# Arduino_Electronic_Load_Ver03.net
KiCad netlist of a schematic drawn in EAGLE
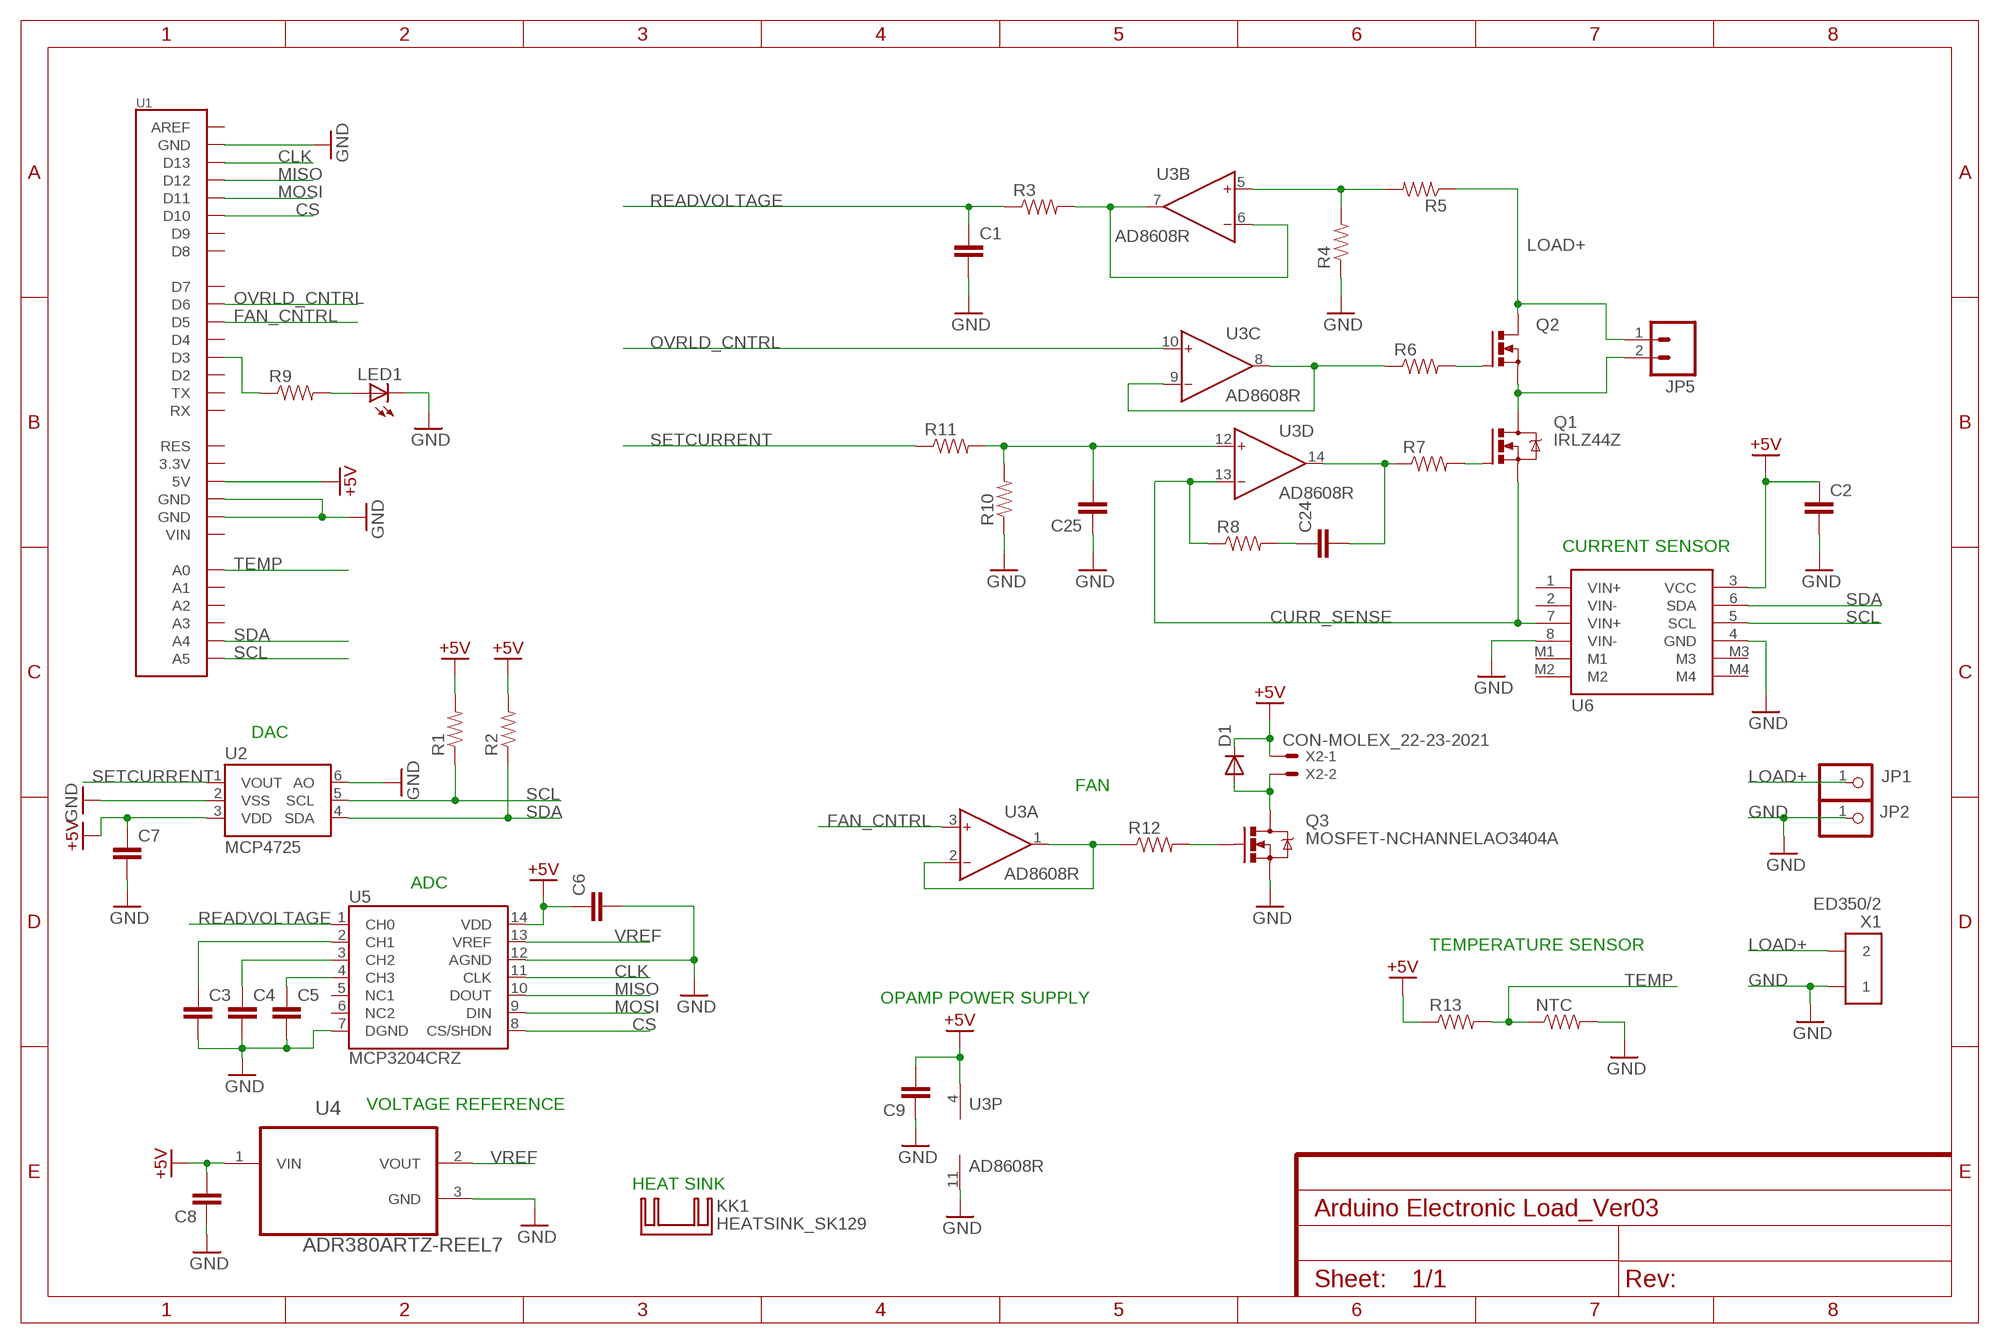
[diagram p0: schematic, sheet 1]

(export (version "E")
  (design (tool "Eeschema 10.0.6"))
  (components
    (comp (ref "C1")
      (value "CAP0603-CAP")
      (footprint "eagle-import:0603-CAP")
      (libsource (lib "eagle-import") (part "CAP0603-CAP"))
    )
    (comp (ref "C2")
      (value "CAP0603-CAP")
      (footprint "eagle-import:0603-CAP")
      (libsource (lib "eagle-import") (part "CAP0603-CAP"))
    )
    (comp (ref "C3")
      (value "CAP0603-CAP")
      (footprint "eagle-import:0603-CAP")
      (libsource (lib "eagle-import") (part "CAP0603-CAP"))
    )
    (comp (ref "C4")
      (value "CAP0603-CAP")
      (footprint "eagle-import:0603-CAP")
      (libsource (lib "eagle-import") (part "CAP0603-CAP"))
    )
    (comp (ref "C5")
      (value "CAP0603-CAP")
      (footprint "eagle-import:0603-CAP")
      (libsource (lib "eagle-import") (part "CAP0603-CAP"))
    )
    (comp (ref "C6")
      (value "CAP0603-CAP")
      (footprint "eagle-import:0603-CAP")
      (libsource (lib "eagle-import") (part "CAP0603-CAP"))
    )
    (comp (ref "C7")
      (value "CAP0603-CAP")
      (footprint "eagle-import:0603-CAP")
      (libsource (lib "eagle-import") (part "CAP0603-CAP"))
    )
    (comp (ref "C8")
      (value "CAP0603-CAP")
      (footprint "eagle-import:0603-CAP")
      (libsource (lib "eagle-import") (part "CAP0603-CAP"))
    )
    (comp (ref "C9")
      (value "CAP0603-CAP")
      (footprint "eagle-import:0603-CAP")
      (libsource (lib "eagle-import") (part "CAP0603-CAP"))
    )
    (comp (ref "C24")
      (value "CAP0603-CAP")
      (footprint "eagle-import:0603-CAP")
      (libsource (lib "eagle-import") (part "CAP0603-CAP"))
    )
    (comp (ref "C25")
      (value "CAP0603-CAP")
      (footprint "eagle-import:0603-CAP")
      (libsource (lib "eagle-import") (part "CAP0603-CAP"))
    )
    (comp (ref "D1")
      (value "DIODEPTH")
      (footprint "eagle-import:DIODE-1N4001")
      (libsource (lib "eagle-import") (part "DIODEPTH"))
    )
    (comp (ref "JP1")
      (value "PINHEAD_PINHD-1X1")
      (footprint "eagle-import:PINHEAD_1X01")
      (libsource (lib "eagle-import") (part "PINHEAD_PINHD-1X1"))
    )
    (comp (ref "JP2")
      (value "PINHEAD_PINHD-1X1")
      (footprint "eagle-import:PINHEAD_1X01")
      (libsource (lib "eagle-import") (part "PINHEAD_PINHD-1X1"))
    )
    (comp (ref "JP5")
      (value "M02")
      (footprint "eagle-import:1X02_LONGPADS")
      (libsource (lib "eagle-import") (part "M02"))
    )
    (comp (ref "KK1")
      (value "HEATSINK_SK129")
      (footprint "eagle-import:HEATSINK_SK129-HOLE")
      (libsource (lib "eagle-import") (part "HEATSINK_SK129"))
    )
    (comp (ref "LED1")
      (value "LED5MM")
      (footprint "eagle-import:LED5MM")
      (libsource (lib "eagle-import") (part "LED5MM"))
    )
    (comp (ref "NTC")
      (value "RESISTOR0402-RES")
      (footprint "eagle-import:0402-RES")
      (libsource (lib "eagle-import") (part "RESISTOR0402-RES"))
    )
    (comp (ref "Q1")
      (value "IRLZ44Z")
      (footprint "eagle-import:TO220BV_1")
      (libsource (lib "eagle-import") (part "IRLZ44Z"))
    )
    (comp (ref "Q2")
      (value "PMOSFET_NTO220BV")
      (footprint "eagle-import:TO220BV")
      (libsource (lib "eagle-import") (part "PMOSFET_NTO220BV"))
    )
    (comp (ref "Q3")
      (value "MOSFET-NCHANNELAO3404A")
      (footprint "eagle-import:SOT23-3")
      (libsource (lib "eagle-import") (part "MOSFET-NCHANNELAO3404A"))
    )
    (comp (ref "R1")
      (value "RESISTOR0603-RES")
      (footprint "eagle-import:0603-RES")
      (libsource (lib "eagle-import") (part "RESISTOR0603-RES"))
    )
    (comp (ref "R2")
      (value "RESISTOR0603-RES")
      (footprint "eagle-import:0603-RES")
      (libsource (lib "eagle-import") (part "RESISTOR0603-RES"))
    )
    (comp (ref "R3")
      (value "RESISTOR0603-RES")
      (footprint "eagle-import:0603-RES")
      (libsource (lib "eagle-import") (part "RESISTOR0603-RES"))
    )
    (comp (ref "R4")
      (value "RESISTOR0603-RES")
      (footprint "eagle-import:0603-RES")
      (libsource (lib "eagle-import") (part "RESISTOR0603-RES"))
    )
    (comp (ref "R5")
      (value "RESISTOR0603-RES")
      (footprint "eagle-import:0603-RES")
      (libsource (lib "eagle-import") (part "RESISTOR0603-RES"))
    )
    (comp (ref "R6")
      (value "RESISTOR0603-RES")
      (footprint "eagle-import:0603-RES")
      (libsource (lib "eagle-import") (part "RESISTOR0603-RES"))
    )
    (comp (ref "R7")
      (value "RESISTOR0603-RES")
      (footprint "eagle-import:0603-RES")
      (libsource (lib "eagle-import") (part "RESISTOR0603-RES"))
    )
    (comp (ref "R8")
      (value "RESISTOR0603-RES")
      (footprint "eagle-import:0603-RES")
      (libsource (lib "eagle-import") (part "RESISTOR0603-RES"))
    )
    (comp (ref "R9")
      (value "RESISTOR0603-RES")
      (footprint "eagle-import:0603-RES")
      (libsource (lib "eagle-import") (part "RESISTOR0603-RES"))
    )
    (comp (ref "R10")
      (value "RESISTOR0603-RES")
      (footprint "eagle-import:0603-RES")
      (libsource (lib "eagle-import") (part "RESISTOR0603-RES"))
    )
    (comp (ref "R11")
      (value "RESISTOR0603-RES")
      (footprint "eagle-import:0603-RES")
      (libsource (lib "eagle-import") (part "RESISTOR0603-RES"))
    )
    (comp (ref "R12")
      (value "RESISTOR0603-RES")
      (footprint "eagle-import:0603-RES")
      (libsource (lib "eagle-import") (part "RESISTOR0603-RES"))
    )
    (comp (ref "R13")
      (value "RESISTOR0603-RES")
      (footprint "eagle-import:0603-RES")
      (libsource (lib "eagle-import") (part "RESISTOR0603-RES"))
    )
    (comp (ref "U1")
      (value "ARDUINO_SHIELD")
      (footprint "eagle-import:DUEMILANOVE_SHIELD")
      (libsource (lib "eagle-import") (part "ARDUINO_SHIELD"))
    )
    (comp (ref "U2")
      (value "MCP4725")
      (footprint "eagle-import:SOT23-6")
      (libsource (lib "eagle-import") (part "MCP4725SOT-23"))
    )
    (comp (ref "U3")
      (value "AD8608R")
      (footprint "eagle-import:SO14")
      (libsource (lib "eagle-import") (part "AD8608R"))
    )
    (comp (ref "U4")
      (value "ADR380ARTZ-REEL7")
      (footprint "eagle-import:SOT95P237X112-3N")
      (libsource (lib "eagle-import") (part "ADR380ARTZ-REEL7"))
    )
    (comp (ref "U5")
      (value "MCP3204CRZ")
      (footprint "eagle-import:SOIC-14")
      (libsource (lib "eagle-import") (part "MCP3204CRZ"))
    )
    (comp (ref "U6")
      (value "INA219")
      (footprint "eagle-import:INA219")
      (libsource (lib "eagle-import") (part "INA219"))
    )
    (comp (ref "X1")
      (value "ED350/2")
      (footprint "eagle-import:ED350_2")
      (libsource (lib "eagle-import") (part "ED350/2"))
    )
    (comp (ref "X2")
      (value "CON-MOLEX_22-23-2021")
      (footprint "eagle-import:CON-MOLEX_22-23-2021")
      (fields (field (name "MF") "MOLEX") (field (name "MPN") "22-23-2021"))
      (libsource (lib "eagle-import") (part "CON-MOLEX_22-23-2021"))
    )
  )
  (nets
    (net (code "1") (name "+5V") (class "Default")
      (node (ref "C2") (pin "1") (pinfunction "1_1") (pintype "passive"))
      (node (ref "C6") (pin "1") (pinfunction "1_1") (pintype "passive"))
      (node (ref "C7") (pin "1") (pinfunction "1_1") (pintype "passive"))
      (node (ref "C8") (pin "2") (pinfunction "2_2") (pintype "passive"))
      (node (ref "C9") (pin "2") (pinfunction "2_2") (pintype "passive"))
      (node (ref "D1") (pin "C") (pinfunction "C_C") (pintype "passive"))
      (node (ref "R1") (pin "2") (pinfunction "2_2") (pintype "passive"))
      (node (ref "R13") (pin "1") (pinfunction "1_1") (pintype "passive"))
      (node (ref "R2") (pin "2") (pinfunction "2_2") (pintype "passive"))
      (node (ref "U1") (pin "5V") (pinfunction "5V_5V") (pintype "bidirectional"))
      (node (ref "U2") (pin "3") (pinfunction "VDD_3") (pintype "bidirectional"))
      (node (ref "U3") (pin "4") (pinfunction "V+_4") (pintype "power_in"))
      (node (ref "U4") (pin "1") (pinfunction "VIN_1") (pintype "passive"))
      (node (ref "U5") (pin "14") (pinfunction "VDD_14") (pintype "bidirectional"))
      (node (ref "U6") (pin "3") (pinfunction "VCC_3") (pintype "bidirectional"))
      (node (ref "X2") (pin "1") (pinfunction "S_1") (pintype "passive"))
    )
    (net (code "2") (name "/CLK") (class "Default")
      (node (ref "U1") (pin "D13") (pinfunction "D13_D13") (pintype "bidirectional"))
      (node (ref "U5") (pin "11") (pinfunction "CLK_11") (pintype "bidirectional"))
    )
    (net (code "3") (name "/CS") (class "Default")
      (node (ref "U1") (pin "D10") (pinfunction "D10_D10") (pintype "bidirectional"))
      (node (ref "U5") (pin "8") (pinfunction "CS/SHDN_8") (pintype "bidirectional"))
    )
    (net (code "4") (name "/CURR_SENSE") (class "Default")
      (node (ref "Q1") (pin "S") (pinfunction "S_S") (pintype "passive"))
      (node (ref "R8") (pin "1") (pinfunction "1_1") (pintype "passive"))
      (node (ref "U3") (pin "13") (pinfunction "IN-_13") (pintype "input"))
      (node (ref "U6") (pin "7") (pinfunction "VIN+_7") (pintype "bidirectional"))
    )
    (net (code "5") (name "/FAN_CNTRL") (class "Default")
      (node (ref "U1") (pin "D5") (pinfunction "D5_D5") (pintype "bidirectional"))
      (node (ref "U3") (pin "3") (pinfunction "IN+_3") (pintype "input"))
    )
    (net (code "6") (name "/LOAD+") (class "Default")
      (node (ref "JP1") (pin "1") (pinfunction "1_1") (pintype "passive"))
      (node (ref "JP5") (pin "1") (pinfunction "1_1") (pintype "passive"))
      (node (ref "Q2") (pin "D") (pinfunction "D_D") (pintype "passive"))
      (node (ref "R5") (pin "1") (pinfunction "1_1") (pintype "passive"))
      (node (ref "X1") (pin "P$2") (pinfunction "2_P$2") (pintype "bidirectional"))
    )
    (net (code "7") (name "/MISO") (class "Default")
      (node (ref "U1") (pin "D12") (pinfunction "D12_D12") (pintype "bidirectional"))
      (node (ref "U5") (pin "10") (pinfunction "DOUT_10") (pintype "bidirectional"))
    )
    (net (code "8") (name "/MOSI") (class "Default")
      (node (ref "U1") (pin "D11") (pinfunction "D11_D11") (pintype "bidirectional"))
      (node (ref "U5") (pin "9") (pinfunction "DIN_9") (pintype "bidirectional"))
    )
    (net (code "9") (name "/OVRLD_CNTRL") (class "Default")
      (node (ref "U1") (pin "D6") (pinfunction "D6_D6") (pintype "bidirectional"))
      (node (ref "U3") (pin "10") (pinfunction "IN+_10") (pintype "input"))
    )
    (net (code "10") (name "/READVOLTAGE") (class "Default")
      (node (ref "C1") (pin "1") (pinfunction "1_1") (pintype "passive"))
      (node (ref "R3") (pin "1") (pinfunction "1_1") (pintype "passive"))
      (node (ref "U5") (pin "1") (pinfunction "CH0_1") (pintype "bidirectional"))
    )
    (net (code "11") (name "/SCL") (class "Default")
      (node (ref "R1") (pin "1") (pinfunction "1_1") (pintype "passive"))
      (node (ref "U1") (pin "A5") (pinfunction "A5_A5") (pintype "bidirectional"))
      (node (ref "U2") (pin "5") (pinfunction "SCL_5") (pintype "bidirectional"))
      (node (ref "U6") (pin "5") (pinfunction "SCL_5") (pintype "bidirectional"))
    )
    (net (code "12") (name "/SDA") (class "Default")
      (node (ref "R2") (pin "1") (pinfunction "1_1") (pintype "passive"))
      (node (ref "U1") (pin "A4") (pinfunction "A4_A4") (pintype "bidirectional"))
      (node (ref "U2") (pin "4") (pinfunction "SDA_4") (pintype "bidirectional"))
      (node (ref "U6") (pin "6") (pinfunction "SDA_6") (pintype "bidirectional"))
    )
    (net (code "13") (name "/SETCURRENT") (class "Default")
      (node (ref "R11") (pin "1") (pinfunction "1_1") (pintype "passive"))
      (node (ref "U2") (pin "1") (pinfunction "VOUT_1") (pintype "bidirectional"))
    )
    (net (code "14") (name "/TEMP") (class "Default")
      (node (ref "NTC") (pin "1") (pinfunction "1_1") (pintype "passive"))
      (node (ref "R13") (pin "2") (pinfunction "2_2") (pintype "passive"))
      (node (ref "U1") (pin "A0") (pinfunction "A0_A0") (pintype "bidirectional"))
    )
    (net (code "15") (name "/VREF") (class "Default")
      (node (ref "U4") (pin "2") (pinfunction "VOUT_2") (pintype "passive"))
      (node (ref "U5") (pin "13") (pinfunction "VREF_13") (pintype "bidirectional"))
    )
    (net (code "16") (name "GND") (class "Default")
      (node (ref "C1") (pin "2") (pinfunction "2_2") (pintype "passive"))
      (node (ref "C2") (pin "2") (pinfunction "2_2") (pintype "passive"))
      (node (ref "C25") (pin "1") (pinfunction "1_1") (pintype "passive"))
      (node (ref "C3") (pin "2") (pinfunction "2_2") (pintype "passive"))
      (node (ref "C4") (pin "2") (pinfunction "2_2") (pintype "passive"))
      (node (ref "C5") (pin "2") (pinfunction "2_2") (pintype "passive"))
      (node (ref "C6") (pin "2") (pinfunction "2_2") (pintype "passive"))
      (node (ref "C7") (pin "2") (pinfunction "2_2") (pintype "passive"))
      (node (ref "C8") (pin "1") (pinfunction "1_1") (pintype "passive"))
      (node (ref "C9") (pin "1") (pinfunction "1_1") (pintype "passive"))
      (node (ref "JP2") (pin "1") (pinfunction "1_1") (pintype "passive"))
      (node (ref "LED1") (pin "K") (pinfunction "C_K") (pintype "passive"))
      (node (ref "NTC") (pin "2") (pinfunction "2_2") (pintype "passive"))
      (node (ref "Q3") (pin "2") (pinfunction "S_2") (pintype "passive"))
      (node (ref "R10") (pin "1") (pinfunction "1_1") (pintype "passive"))
      (node (ref "R4") (pin "1") (pinfunction "1_1") (pintype "passive"))
      (node (ref "U1") (pin "GND@0") (pinfunction "GND_GND@0") (pintype "bidirectional"))
      (node (ref "U1") (pin "GND@1") (pinfunction "GND_GND@1") (pintype "bidirectional"))
      (node (ref "U1") (pin "GND@2") (pinfunction "GND_GND@2") (pintype "bidirectional"))
      (node (ref "U2") (pin "2") (pinfunction "VSS_2") (pintype "bidirectional"))
      (node (ref "U2") (pin "6") (pinfunction "AO_6") (pintype "bidirectional"))
      (node (ref "U3") (pin "11") (pinfunction "V-_11") (pintype "power_in"))
      (node (ref "U4") (pin "3") (pinfunction "GND_3") (pintype "passive"))
      (node (ref "U5") (pin "12") (pinfunction "AGND_12") (pintype "bidirectional"))
      (node (ref "U5") (pin "7") (pinfunction "DGND_7") (pintype "bidirectional"))
      (node (ref "U6") (pin "4") (pinfunction "GND_4") (pintype "bidirectional"))
      (node (ref "U6") (pin "8") (pinfunction "VIN-_8") (pintype "bidirectional"))
      (node (ref "X1") (pin "P$1") (pinfunction "1_P$1") (pintype "bidirectional"))
    )
    (net (code "17") (name "Net-(C24-Pad1)") (class "Default")
      (node (ref "C24") (pin "1") (pinfunction "1_1") (pintype "passive"))
      (node (ref "R8") (pin "2") (pinfunction "2_2") (pintype "passive"))
    )
    (net (code "18") (name "Net-(JP5-Pad2)") (class "Default")
      (node (ref "JP5") (pin "2") (pinfunction "2_2") (pintype "passive"))
      (node (ref "Q1") (pin "D") (pinfunction "D_D") (pintype "passive"))
      (node (ref "Q2") (pin "S") (pinfunction "S_S") (pintype "passive"))
    )
    (net (code "19") (name "Net-(LED1-PadA)") (class "Default")
      (node (ref "LED1") (pin "A") (pinfunction "A_A") (pintype "passive"))
      (node (ref "R9") (pin "2") (pinfunction "2_2") (pintype "passive"))
    )
    (net (code "20") (name "Net-(Q1-PadG)") (class "Default")
      (node (ref "Q1") (pin "G") (pinfunction "G_G") (pintype "passive"))
      (node (ref "R7") (pin "2") (pinfunction "2_2") (pintype "passive"))
    )
    (net (code "21") (name "Net-(Q2-PadG)") (class "Default")
      (node (ref "Q2") (pin "G") (pinfunction "G_G") (pintype "passive"))
      (node (ref "R6") (pin "2") (pinfunction "2_2") (pintype "passive"))
    )
    (net (code "22") (name "Net-(Q3-D)") (class "Default")
      (node (ref "D1") (pin "A") (pinfunction "A_A") (pintype "passive"))
      (node (ref "Q3") (pin "3") (pinfunction "D_3") (pintype "passive"))
      (node (ref "X2") (pin "2") (pinfunction "S_2") (pintype "passive"))
    )
    (net (code "23") (name "Net-(Q3-G)") (class "Default")
      (node (ref "Q3") (pin "1") (pinfunction "G_1") (pintype "passive"))
      (node (ref "R12") (pin "2") (pinfunction "2_2") (pintype "passive"))
    )
    (net (code "24") (name "Net-(R9-Pad1)") (class "Default")
      (node (ref "R9") (pin "1") (pinfunction "1_1") (pintype "passive"))
      (node (ref "U1") (pin "D3") (pinfunction "D3_D3") (pintype "bidirectional"))
    )
    (net (code "25") (name "Net-(U3A-IN-)") (class "Default")
      (node (ref "R12") (pin "1") (pinfunction "1_1") (pintype "passive"))
      (node (ref "U3") (pin "1") (pinfunction "OUT_1") (pintype "output"))
      (node (ref "U3") (pin "2") (pinfunction "IN-_2") (pintype "input"))
    )
    (net (code "26") (name "Net-(U3B-IN+)") (class "Default")
      (node (ref "R4") (pin "2") (pinfunction "2_2") (pintype "passive"))
      (node (ref "R5") (pin "2") (pinfunction "2_2") (pintype "passive"))
      (node (ref "U3") (pin "5") (pinfunction "IN+_5") (pintype "input"))
    )
    (net (code "27") (name "Net-(U3B-IN-)") (class "Default")
      (node (ref "R3") (pin "2") (pinfunction "2_2") (pintype "passive"))
      (node (ref "U3") (pin "6") (pinfunction "IN-_6") (pintype "input"))
      (node (ref "U3") (pin "7") (pinfunction "OUT_7") (pintype "output"))
    )
    (net (code "28") (name "Net-(U3C-IN-)") (class "Default")
      (node (ref "R6") (pin "1") (pinfunction "1_1") (pintype "passive"))
      (node (ref "U3") (pin "8") (pinfunction "OUT_8") (pintype "output"))
      (node (ref "U3") (pin "9") (pinfunction "IN-_9") (pintype "input"))
    )
    (net (code "29") (name "Net-(U3D-IN+)") (class "Default")
      (node (ref "C25") (pin "2") (pinfunction "2_2") (pintype "passive"))
      (node (ref "R10") (pin "2") (pinfunction "2_2") (pintype "passive"))
      (node (ref "R11") (pin "2") (pinfunction "2_2") (pintype "passive"))
      (node (ref "U3") (pin "12") (pinfunction "IN+_12") (pintype "input"))
    )
    (net (code "30") (name "Net-(U3D-OUT)") (class "Default")
      (node (ref "C24") (pin "2") (pinfunction "2_2") (pintype "passive"))
      (node (ref "R7") (pin "1") (pinfunction "1_1") (pintype "passive"))
      (node (ref "U3") (pin "14") (pinfunction "OUT_14") (pintype "output"))
    )
    (net (code "31") (name "Net-(U5-CH1)") (class "Default")
      (node (ref "C3") (pin "1") (pinfunction "1_1") (pintype "passive"))
      (node (ref "U5") (pin "2") (pinfunction "CH1_2") (pintype "bidirectional"))
    )
    (net (code "32") (name "Net-(U5-CH2)") (class "Default")
      (node (ref "C4") (pin "1") (pinfunction "1_1") (pintype "passive"))
      (node (ref "U5") (pin "3") (pinfunction "CH2_3") (pintype "bidirectional"))
    )
    (net (code "33") (name "Net-(U5-CH3)") (class "Default")
      (node (ref "C5") (pin "1") (pinfunction "1_1") (pintype "passive"))
      (node (ref "U5") (pin "4") (pinfunction "CH3_4") (pintype "bidirectional"))
    )
    (net (code "34") (name "unconnected-(U1-Pad3.3V)") (class "Default")
      (node (ref "U1") (pin "3.3V") (pinfunction "3.3V_3.3V") (pintype "bidirectional"))
    )
    (net (code "35") (name "unconnected-(U1-PadA1)") (class "Default")
      (node (ref "U1") (pin "A1") (pinfunction "A1_A1") (pintype "bidirectional"))
    )
    (net (code "36") (name "unconnected-(U1-PadA2)") (class "Default")
      (node (ref "U1") (pin "A2") (pinfunction "A2_A2") (pintype "bidirectional"))
    )
    (net (code "37") (name "unconnected-(U1-PadA3)") (class "Default")
      (node (ref "U1") (pin "A3") (pinfunction "A3_A3") (pintype "bidirectional"))
    )
    (net (code "38") (name "unconnected-(U1-PadAREF)") (class "Default")
      (node (ref "U1") (pin "AREF") (pinfunction "AREF_AREF") (pintype "bidirectional"))
    )
    (net (code "39") (name "unconnected-(U1-PadD2)") (class "Default")
      (node (ref "U1") (pin "D2") (pinfunction "D2_D2") (pintype "bidirectional"))
    )
    (net (code "40") (name "unconnected-(U1-PadD4)") (class "Default")
      (node (ref "U1") (pin "D4") (pinfunction "D4_D4") (pintype "bidirectional"))
    )
    (net (code "41") (name "unconnected-(U1-PadD7)") (class "Default")
      (node (ref "U1") (pin "D7") (pinfunction "D7_D7") (pintype "bidirectional"))
    )
    (net (code "42") (name "unconnected-(U1-PadD8)") (class "Default")
      (node (ref "U1") (pin "D8") (pinfunction "D8_D8") (pintype "bidirectional"))
    )
    (net (code "43") (name "unconnected-(U1-PadD9)") (class "Default")
      (node (ref "U1") (pin "D9") (pinfunction "D9_D9") (pintype "bidirectional"))
    )
    (net (code "44") (name "unconnected-(U1-PadRES)") (class "Default")
      (node (ref "U1") (pin "RES") (pinfunction "RES_RES") (pintype "bidirectional"))
    )
    (net (code "45") (name "unconnected-(U1-PadRX)") (class "Default")
      (node (ref "U1") (pin "RX") (pinfunction "RX_RX") (pintype "bidirectional"))
    )
    (net (code "46") (name "unconnected-(U1-PadTX)") (class "Default")
      (node (ref "U1") (pin "TX") (pinfunction "TX_TX") (pintype "bidirectional"))
    )
    (net (code "47") (name "unconnected-(U1-PadVIN)") (class "Default")
      (node (ref "U1") (pin "VIN") (pinfunction "VIN_VIN") (pintype "bidirectional"))
    )
    (net (code "48") (name "unconnected-(U5-NC1-Pad5)") (class "Default")
      (node (ref "U5") (pin "5") (pinfunction "NC1_5") (pintype "bidirectional"))
    )
    (net (code "49") (name "unconnected-(U5-NC2-Pad6)") (class "Default")
      (node (ref "U5") (pin "6") (pinfunction "NC2_6") (pintype "bidirectional"))
    )
    (net (code "50") (name "unconnected-(U6-PadM1)") (class "Default")
      (node (ref "U6") (pin "M1") (pinfunction "M1_M1") (pintype "bidirectional"))
    )
    (net (code "51") (name "unconnected-(U6-PadM2)") (class "Default")
      (node (ref "U6") (pin "M2") (pinfunction "M2_M2") (pintype "bidirectional"))
    )
    (net (code "52") (name "unconnected-(U6-PadM3)") (class "Default")
      (node (ref "U6") (pin "M3") (pinfunction "M3_M3") (pintype "bidirectional"))
    )
    (net (code "53") (name "unconnected-(U6-PadM4)") (class "Default")
      (node (ref "U6") (pin "M4") (pinfunction "M4_M4") (pintype "bidirectional"))
    )
    (net (code "54") (name "unconnected-(U6-VIN+-Pad1)") (class "Default")
      (node (ref "U6") (pin "1") (pinfunction "VIN+_1") (pintype "bidirectional"))
    )
    (net (code "55") (name "unconnected-(U6-VIN--Pad2)") (class "Default")
      (node (ref "U6") (pin "2") (pinfunction "VIN-_2") (pintype "bidirectional"))
    )
  )
)
